# SRAM.net
KiCad netlist of a schematic drawn in Altium Designer
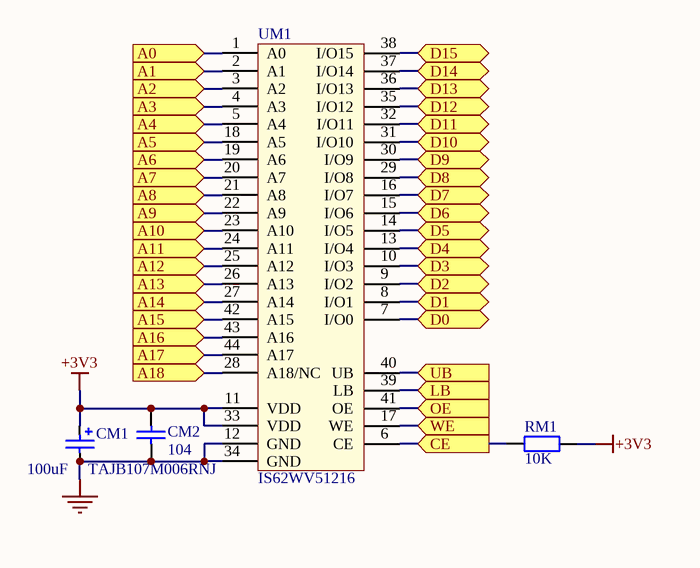
[diagram p0: SRAM.SchDoc]

(export (version "E")
  (design (tool "Eeschema 10.0.6"))
  (components
    (comp (ref "CM1")
      (value "100uF     TAJB107M006RNJ")
      (footprint "CAP_TAN_B_3518")
      (description "Capacitor")
      (fields (field (name "Comment") "Cap_Tan"))
      (libsource (lib "Peace的集成库") (part "Cap_Tan"))
    )
    (comp (ref "CM2")
      (value "104")
      (footprint "CAPC1608N")
      (description "Capacitor")
      (fields (field (name "Comment") "Cap1") (field (name "PUBLISHER") "Altium Limited"))
      (libsource (lib "Peace的集成库") (part "Cap1"))
    )
    (comp (ref "RM1")
      (value "10K")
      (footprint "RESC1608N")
      (description "Resistor")
      (fields (field (name "Comment") "Res1") (field (name "PUBLISHER") "Altium Limited"))
      (libsource (lib "Peace的集成库") (part "Res1"))
    )
    (comp (ref "UM1")
      (value "IS62WV51216")
      (footprint "TSOP44")
      (libsource (lib "Peace的集成库") (part "IS61LV51216"))
    )
  )
  (nets
    (net (code "1") (name "+3V3") (class "Default")
      (node (ref "CM1") (pin "1") (pinfunction "1_1") (pintype "passive"))
      (node (ref "CM2") (pin "2") (pinfunction "2_2") (pintype "passive"))
      (node (ref "RM1") (pin "1") (pinfunction "1_1") (pintype "passive"))
      (node (ref "UM1") (pin "11") (pinfunction "VDD_11") (pintype "passive"))
      (node (ref "UM1") (pin "33") (pinfunction "VDD_33") (pintype "passive"))
    )
    (net (code "2") (name "/A0") (class "Default")
      (node (ref "UM1") (pin "1") (pinfunction "A0_1") (pintype "passive"))
    )
    (net (code "3") (name "/A1") (class "Default")
      (node (ref "UM1") (pin "2") (pinfunction "A1_2") (pintype "passive"))
    )
    (net (code "4") (name "/A2") (class "Default")
      (node (ref "UM1") (pin "3") (pinfunction "A2_3") (pintype "passive"))
    )
    (net (code "5") (name "/A3") (class "Default")
      (node (ref "UM1") (pin "4") (pinfunction "A3_4") (pintype "passive"))
    )
    (net (code "6") (name "/A4") (class "Default")
      (node (ref "UM1") (pin "5") (pinfunction "A4_5") (pintype "passive"))
    )
    (net (code "7") (name "/A5") (class "Default")
      (node (ref "UM1") (pin "18") (pinfunction "A5_18") (pintype "passive"))
    )
    (net (code "8") (name "/A6") (class "Default")
      (node (ref "UM1") (pin "19") (pinfunction "A6_19") (pintype "passive"))
    )
    (net (code "9") (name "/A7") (class "Default")
      (node (ref "UM1") (pin "20") (pinfunction "A7_20") (pintype "passive"))
    )
    (net (code "10") (name "/A8") (class "Default")
      (node (ref "UM1") (pin "21") (pinfunction "A8_21") (pintype "passive"))
    )
    (net (code "11") (name "/A9") (class "Default")
      (node (ref "UM1") (pin "22") (pinfunction "A9_22") (pintype "passive"))
    )
    (net (code "12") (name "/A10") (class "Default")
      (node (ref "UM1") (pin "23") (pinfunction "A10_23") (pintype "passive"))
    )
    (net (code "13") (name "/A11") (class "Default")
      (node (ref "UM1") (pin "24") (pinfunction "A11_24") (pintype "passive"))
    )
    (net (code "14") (name "/A12") (class "Default")
      (node (ref "UM1") (pin "25") (pinfunction "A12_25") (pintype "passive"))
    )
    (net (code "15") (name "/A13") (class "Default")
      (node (ref "UM1") (pin "26") (pinfunction "A13_26") (pintype "passive"))
    )
    (net (code "16") (name "/A14") (class "Default")
      (node (ref "UM1") (pin "27") (pinfunction "A14_27") (pintype "passive"))
    )
    (net (code "17") (name "/A15") (class "Default")
      (node (ref "UM1") (pin "42") (pinfunction "A15_42") (pintype "passive"))
    )
    (net (code "18") (name "/A16") (class "Default")
      (node (ref "UM1") (pin "43") (pinfunction "A16_43") (pintype "passive"))
    )
    (net (code "19") (name "/A17") (class "Default")
      (node (ref "UM1") (pin "44") (pinfunction "A17_44") (pintype "passive"))
    )
    (net (code "20") (name "/A18") (class "Default")
      (node (ref "UM1") (pin "28") (pinfunction "A18/NC_28") (pintype "passive"))
    )
    (net (code "21") (name "/CE") (class "Default")
      (node (ref "RM1") (pin "2") (pinfunction "2_2") (pintype "passive"))
      (node (ref "UM1") (pin "6") (pinfunction "CE_6") (pintype "passive"))
    )
    (net (code "22") (name "/D0") (class "Default")
      (node (ref "UM1") (pin "7") (pinfunction "I/O0_7") (pintype "passive"))
    )
    (net (code "23") (name "/D1") (class "Default")
      (node (ref "UM1") (pin "8") (pinfunction "I/O1_8") (pintype "passive"))
    )
    (net (code "24") (name "/D2") (class "Default")
      (node (ref "UM1") (pin "9") (pinfunction "I/O2_9") (pintype "passive"))
    )
    (net (code "25") (name "/D3") (class "Default")
      (node (ref "UM1") (pin "10") (pinfunction "I/O3_10") (pintype "passive"))
    )
    (net (code "26") (name "/D4") (class "Default")
      (node (ref "UM1") (pin "13") (pinfunction "I/O4_13") (pintype "passive"))
    )
    (net (code "27") (name "/D5") (class "Default")
      (node (ref "UM1") (pin "14") (pinfunction "I/O5_14") (pintype "passive"))
    )
    (net (code "28") (name "/D6") (class "Default")
      (node (ref "UM1") (pin "15") (pinfunction "I/O6_15") (pintype "passive"))
    )
    (net (code "29") (name "/D7") (class "Default")
      (node (ref "UM1") (pin "16") (pinfunction "I/O7_16") (pintype "passive"))
    )
    (net (code "30") (name "/D8") (class "Default")
      (node (ref "UM1") (pin "29") (pinfunction "I/O8_29") (pintype "passive"))
    )
    (net (code "31") (name "/D9") (class "Default")
      (node (ref "UM1") (pin "30") (pinfunction "I/O9_30") (pintype "passive"))
    )
    (net (code "32") (name "/D10") (class "Default")
      (node (ref "UM1") (pin "31") (pinfunction "I/O10_31") (pintype "passive"))
    )
    (net (code "33") (name "/D11") (class "Default")
      (node (ref "UM1") (pin "32") (pinfunction "I/O11_32") (pintype "passive"))
    )
    (net (code "34") (name "/D12") (class "Default")
      (node (ref "UM1") (pin "35") (pinfunction "I/O12_35") (pintype "passive"))
    )
    (net (code "35") (name "/D13") (class "Default")
      (node (ref "UM1") (pin "36") (pinfunction "I/O13_36") (pintype "passive"))
    )
    (net (code "36") (name "/D14") (class "Default")
      (node (ref "UM1") (pin "37") (pinfunction "I/O14_37") (pintype "passive"))
    )
    (net (code "37") (name "/D15") (class "Default")
      (node (ref "UM1") (pin "38") (pinfunction "I/O15_38") (pintype "passive"))
    )
    (net (code "38") (name "/LB") (class "Default")
      (node (ref "UM1") (pin "39") (pinfunction "LB_39") (pintype "passive"))
    )
    (net (code "39") (name "/OE") (class "Default")
      (node (ref "UM1") (pin "41") (pinfunction "OE_41") (pintype "passive"))
    )
    (net (code "40") (name "/UB") (class "Default")
      (node (ref "UM1") (pin "40") (pinfunction "UB_40") (pintype "passive"))
    )
    (net (code "41") (name "/WE") (class "Default")
      (node (ref "UM1") (pin "17") (pinfunction "WE_17") (pintype "passive"))
    )
    (net (code "42") (name "GND") (class "Default")
      (node (ref "CM1") (pin "2") (pinfunction "2_2") (pintype "passive"))
      (node (ref "CM2") (pin "1") (pinfunction "1_1") (pintype "passive"))
      (node (ref "UM1") (pin "12") (pinfunction "GND_12") (pintype "passive"))
      (node (ref "UM1") (pin "34") (pinfunction "GND_34") (pintype "passive"))
    )
  )
)
